# SCH_robot_arm_2022-02-01.net
KiCad netlist of a schematic drawn in EasyEDA
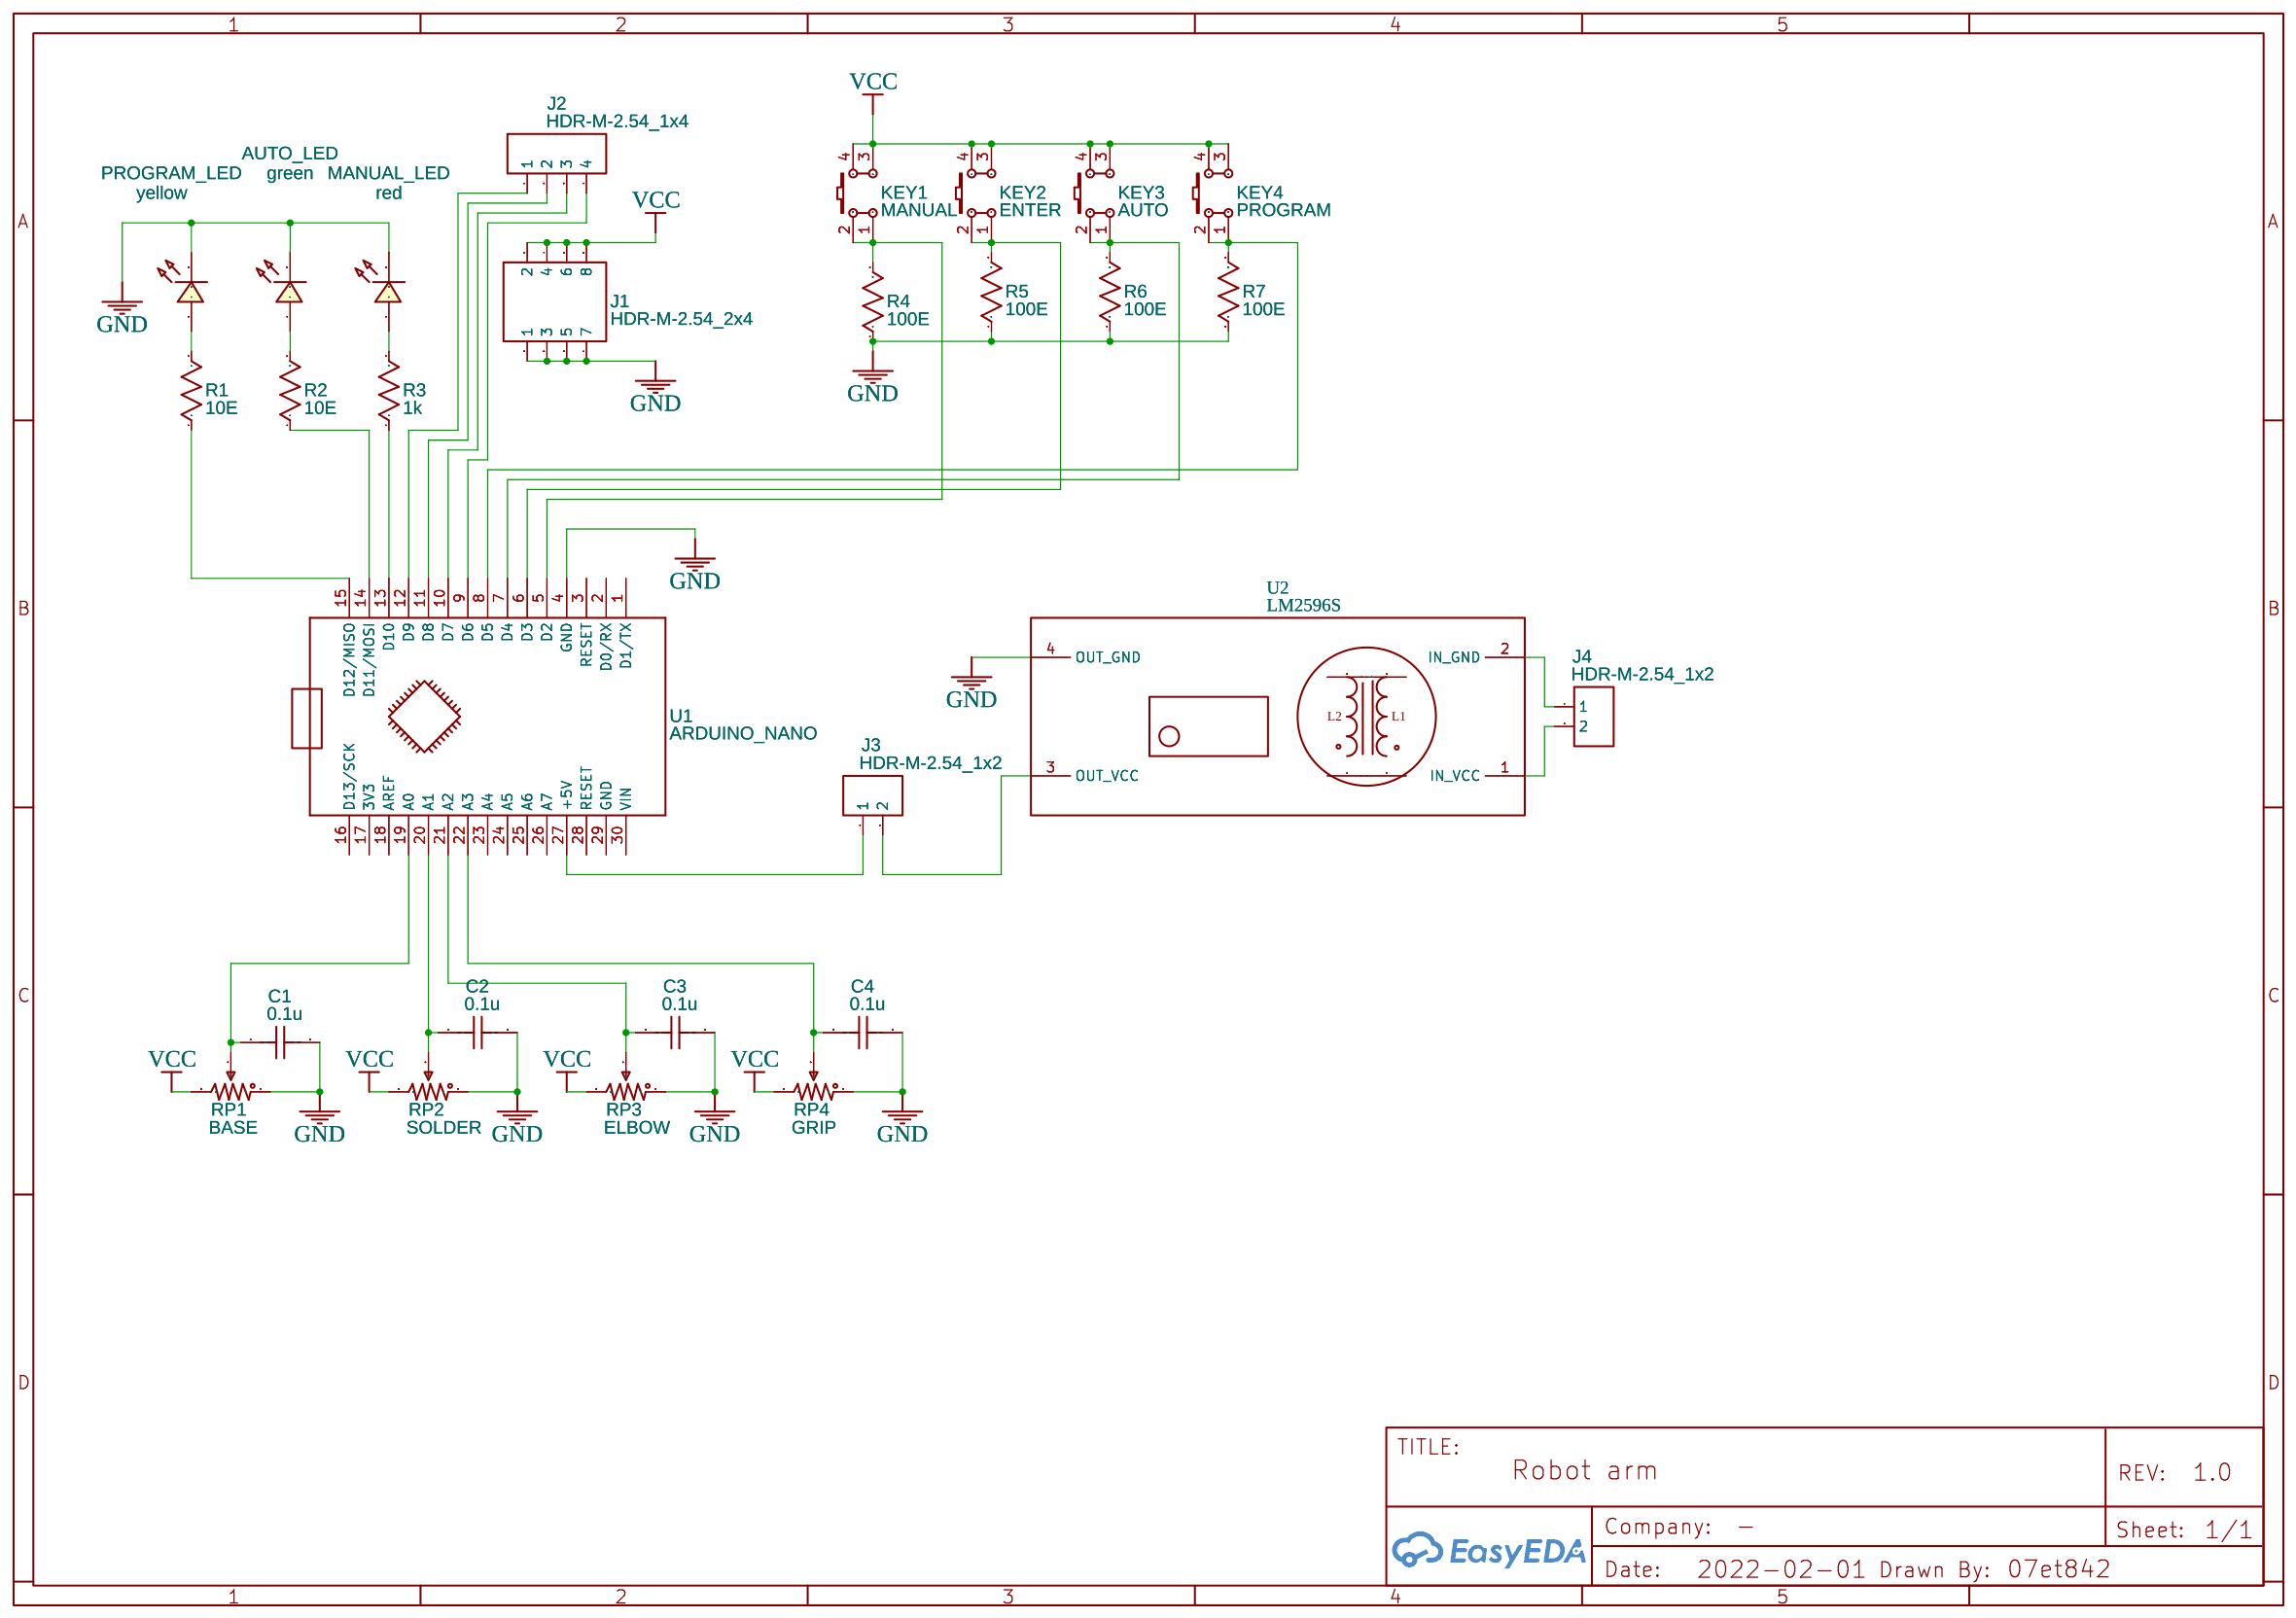
[diagram p0: schematic sheet]

(export (version "E")
  (design (tool "Eeschema 10.0.6"))
  (components
    (comp (ref "AUTO_LED")
      (value "green")
      (fields
        (field (name "BOM_Manufacturer Part") "19-217/R6C-AL1M2VY/3T")
        (field (name "BOM_Supplier Part") "C72044")
      )
      (libsource (lib "") (part "LED-0603_R_1"))
    )
    (comp (ref "C1") (value "0.1u") (libsource (lib "") (part "C_0603_US")))
    (comp (ref "C2") (value "0.1u") (libsource (lib "") (part "C_0603_US")))
    (comp (ref "C3") (value "0.1u") (libsource (lib "") (part "C_0603_US")))
    (comp (ref "C4") (value "0.1u") (libsource (lib "") (part "C_0603_US")))
    (comp (ref "J1")
      (value "HDR-M-2.54_2x4")
      (fields (field (name "BOM_Supplier Part") "C58363"))
      (libsource (lib "") (part "HDR-M-2.54_2x4"))
    )
    (comp (ref "J2")
      (value "HDR-M-2.54_1x4")
      (fields (field (name "BOM_Supplier Part") "C124378"))
      (libsource (lib "") (part "HDR-M-2.54_1x4"))
    )
    (comp (ref "J3")
      (value "HDR-M-2.54_1x2")
      (fields (field (name "BOM_Supplier Part") "C124375"))
      (libsource (lib "") (part "HDR-M-2.54_1x2"))
    )
    (comp (ref "J4")
      (value "HDR-M-2.54_1x2")
      (fields (field (name "BOM_Supplier Part") "C124375"))
      (libsource (lib "") (part "HDR-M-2.54_1x2_1"))
    )
    (comp (ref "KEY1")
      (value "MANUAL")
      (fields
        (field (name "BOM_Manufacturer Part") "K2-1102DP-E4SW-04")
        (field (name "BOM_Supplier Part") "C136684")
      )
      (libsource (lib "") (part "K4-6×6_TH"))
    )
    (comp (ref "KEY2")
      (value "ENTER")
      (fields
        (field (name "BOM_Manufacturer Part") "K2-1102DP-E4SW-04")
        (field (name "BOM_Supplier Part") "C136684")
      )
      (libsource (lib "") (part "K4-6×6_TH"))
    )
    (comp (ref "KEY3")
      (value "AUTO")
      (fields
        (field (name "BOM_Manufacturer Part") "K2-1102DP-E4SW-04")
        (field (name "BOM_Supplier Part") "C136684")
      )
      (libsource (lib "") (part "K4-6×6_TH"))
    )
    (comp (ref "KEY4")
      (value "PROGRAM")
      (fields
        (field (name "BOM_Manufacturer Part") "K2-1102DP-E4SW-04")
        (field (name "BOM_Supplier Part") "C136684")
      )
      (libsource (lib "") (part "K4-6×6_TH"))
    )
    (comp (ref "MANUAL_LED")
      (value "red")
      (fields
        (field (name "BOM_Manufacturer Part") "19-217/R6C-AL1M2VY/3T")
        (field (name "BOM_Supplier Part") "C72044")
      )
      (libsource (lib "") (part "LED-0603_R_2"))
    )
    (comp (ref "PROGRAM_LED")
      (value "yellow")
      (fields
        (field (name "BOM_Manufacturer Part") "19-217/R6C-AL1M2VY/3T")
        (field (name "BOM_Supplier Part") "C72044")
      )
      (libsource (lib "") (part "LED-0603_R"))
    )
    (comp (ref "R1") (value "10E") (libsource (lib "") (part "R_0603_US")))
    (comp (ref "R2") (value "10E") (libsource (lib "") (part "R_0603_US")))
    (comp (ref "R3") (value "1k") (libsource (lib "") (part "R_0603_US")))
    (comp (ref "R4") (value "100E") (libsource (lib "") (part "R_0603_US")))
    (comp (ref "R5") (value "100E") (libsource (lib "") (part "R_0603_US")))
    (comp (ref "R6") (value "100E") (libsource (lib "") (part "R_0603_US")))
    (comp (ref "R7") (value "100E") (libsource (lib "") (part "R_0603_US")))
    (comp (ref "RP1") (value "BASE") (libsource (lib "") (part "R_3386P_US")))
    (comp (ref "RP2") (value "SOLDER") (libsource (lib "") (part "R_3386P_US")))
    (comp (ref "RP3") (value "ELBOW") (libsource (lib "") (part "R_3386P_US")))
    (comp (ref "RP4") (value "GRIP") (libsource (lib "") (part "R_3386P_US")))
    (comp (ref "U1")
      (value "ARDUINO_NANO")
      (fields (field (name "BOM_Manufacturer Part") "?"))
      (libsource (lib "") (part "Unknown_240_-450"))
    )
    (comp (ref "U2") (value "LM2596S") (libsource (lib "") (part "Unknown_645_-450")))
  )
  (nets
    (net (code "1") (name "GND") (class "Default")
      (node (ref "AUTO_LED") (pin "2") (pinfunction "2_2") (pintype "unspecified"))
      (node (ref "C1") (pin "2") (pinfunction "2_2") (pintype "unspecified"))
      (node (ref "C2") (pin "2") (pinfunction "2_2") (pintype "unspecified"))
      (node (ref "C3") (pin "2") (pinfunction "2_2") (pintype "unspecified"))
      (node (ref "C4") (pin "2") (pinfunction "2_2") (pintype "unspecified"))
      (node (ref "J1") (pin "1") (pinfunction "1_1") (pintype "unspecified"))
      (node (ref "J1") (pin "3") (pinfunction "3_3") (pintype "unspecified"))
      (node (ref "J1") (pin "5") (pinfunction "5_5") (pintype "unspecified"))
      (node (ref "J1") (pin "7") (pinfunction "7_7") (pintype "unspecified"))
      (node (ref "MANUAL_LED") (pin "2") (pinfunction "2_2") (pintype "unspecified"))
      (node (ref "PROGRAM_LED") (pin "2") (pinfunction "2_2") (pintype "unspecified"))
      (node (ref "R4") (pin "1") (pinfunction "1_1") (pintype "unspecified"))
      (node (ref "R5") (pin "1") (pinfunction "1_1") (pintype "unspecified"))
      (node (ref "R6") (pin "1") (pinfunction "1_1") (pintype "unspecified"))
      (node (ref "R7") (pin "1") (pinfunction "1_1") (pintype "unspecified"))
      (node (ref "RP1") (pin "1") (pinfunction "1_1") (pintype "unspecified"))
      (node (ref "RP2") (pin "1") (pinfunction "1_1") (pintype "unspecified"))
      (node (ref "RP3") (pin "1") (pinfunction "1_1") (pintype "unspecified"))
      (node (ref "RP4") (pin "1") (pinfunction "1_1") (pintype "unspecified"))
      (node (ref "U1") (pin "4") (pinfunction "GND_4") (pintype "unspecified"))
      (node (ref "U2") (pin "4") (pinfunction "OUT_GND_4") (pintype "unspecified"))
    )
    (net (code "2") (name "Net-(AUTO_LED-Pad1)") (class "Default")
      (node (ref "AUTO_LED") (pin "1") (pinfunction "1_1") (pintype "unspecified"))
      (node (ref "R2") (pin "2") (pinfunction "2_2") (pintype "unspecified"))
    )
    (net (code "3") (name "Net-(MANUAL_LED-Pad1)") (class "Default")
      (node (ref "MANUAL_LED") (pin "1") (pinfunction "1_1") (pintype "unspecified"))
      (node (ref "R3") (pin "2") (pinfunction "2_2") (pintype "unspecified"))
    )
    (net (code "4") (name "Net-(PROGRAM_LED-Pad1)") (class "Default")
      (node (ref "PROGRAM_LED") (pin "1") (pinfunction "1_1") (pintype "unspecified"))
      (node (ref "R1") (pin "2") (pinfunction "2_2") (pintype "unspecified"))
    )
    (net (code "5") (name "Net-(U1-+5V)") (class "Default")
      (node (ref "J3") (pin "1") (pinfunction "1_1") (pintype "unspecified"))
      (node (ref "U1") (pin "27") (pinfunction "+5V_27") (pintype "unspecified"))
    )
    (net (code "6") (name "Net-(U1-A0)") (class "Default")
      (node (ref "C1") (pin "1") (pinfunction "1_1") (pintype "unspecified"))
      (node (ref "RP1") (pin "2") (pinfunction "2_2") (pintype "unspecified"))
      (node (ref "U1") (pin "19") (pinfunction "A0_19") (pintype "unspecified"))
    )
    (net (code "7") (name "Net-(U1-A1)") (class "Default")
      (node (ref "C2") (pin "1") (pinfunction "1_1") (pintype "unspecified"))
      (node (ref "RP2") (pin "2") (pinfunction "2_2") (pintype "unspecified"))
      (node (ref "U1") (pin "20") (pinfunction "A1_20") (pintype "unspecified"))
    )
    (net (code "8") (name "Net-(U1-A2)") (class "Default")
      (node (ref "C3") (pin "1") (pinfunction "1_1") (pintype "unspecified"))
      (node (ref "RP3") (pin "2") (pinfunction "2_2") (pintype "unspecified"))
      (node (ref "U1") (pin "21") (pinfunction "A2_21") (pintype "unspecified"))
    )
    (net (code "9") (name "Net-(U1-A3)") (class "Default")
      (node (ref "C4") (pin "1") (pinfunction "1_1") (pintype "unspecified"))
      (node (ref "RP4") (pin "2") (pinfunction "2_2") (pintype "unspecified"))
      (node (ref "U1") (pin "22") (pinfunction "A3_22") (pintype "unspecified"))
    )
    (net (code "10") (name "Net-(U1-D2)") (class "Default")
      (node (ref "KEY1") (pin "1") (pinfunction "1_1") (pintype "unspecified"))
      (node (ref "KEY1") (pin "2") (pinfunction "2_2") (pintype "unspecified"))
      (node (ref "R4") (pin "2") (pinfunction "2_2") (pintype "unspecified"))
      (node (ref "U1") (pin "5") (pinfunction "D2_5") (pintype "unspecified"))
    )
    (net (code "11") (name "Net-(U1-D3)") (class "Default")
      (node (ref "KEY2") (pin "1") (pinfunction "1_1") (pintype "unspecified"))
      (node (ref "KEY2") (pin "2") (pinfunction "2_2") (pintype "unspecified"))
      (node (ref "R5") (pin "2") (pinfunction "2_2") (pintype "unspecified"))
      (node (ref "U1") (pin "6") (pinfunction "D3_6") (pintype "unspecified"))
    )
    (net (code "12") (name "Net-(U1-D4)") (class "Default")
      (node (ref "KEY3") (pin "1") (pinfunction "1_1") (pintype "unspecified"))
      (node (ref "KEY3") (pin "2") (pinfunction "2_2") (pintype "unspecified"))
      (node (ref "R6") (pin "2") (pinfunction "2_2") (pintype "unspecified"))
      (node (ref "U1") (pin "7") (pinfunction "D4_7") (pintype "unspecified"))
    )
    (net (code "13") (name "Net-(U1-D5)") (class "Default")
      (node (ref "KEY4") (pin "1") (pinfunction "1_1") (pintype "unspecified"))
      (node (ref "KEY4") (pin "2") (pinfunction "2_2") (pintype "unspecified"))
      (node (ref "R7") (pin "2") (pinfunction "2_2") (pintype "unspecified"))
      (node (ref "U1") (pin "8") (pinfunction "D5_8") (pintype "unspecified"))
    )
    (net (code "14") (name "Net-(U1-D6)") (class "Default")
      (node (ref "J2") (pin "4") (pinfunction "4_4") (pintype "unspecified"))
      (node (ref "U1") (pin "9") (pinfunction "D6_9") (pintype "unspecified"))
    )
    (net (code "15") (name "Net-(U1-D7)") (class "Default")
      (node (ref "J2") (pin "3") (pinfunction "3_3") (pintype "unspecified"))
      (node (ref "U1") (pin "10") (pinfunction "D7_10") (pintype "unspecified"))
    )
    (net (code "16") (name "Net-(U1-D8)") (class "Default")
      (node (ref "J2") (pin "2") (pinfunction "2_2") (pintype "unspecified"))
      (node (ref "U1") (pin "11") (pinfunction "D8_11") (pintype "unspecified"))
    )
    (net (code "17") (name "Net-(U1-D9)") (class "Default")
      (node (ref "J2") (pin "1") (pinfunction "1_1") (pintype "unspecified"))
      (node (ref "U1") (pin "12") (pinfunction "D9_12") (pintype "unspecified"))
    )
    (net (code "18") (name "Net-(U1-D10)") (class "Default")
      (node (ref "R3") (pin "1") (pinfunction "1_1") (pintype "unspecified"))
      (node (ref "U1") (pin "13") (pinfunction "D10_13") (pintype "unspecified"))
    )
    (net (code "19") (name "Net-(U1-D11{slash}MOSI)") (class "Default")
      (node (ref "R2") (pin "1") (pinfunction "1_1") (pintype "unspecified"))
      (node (ref "U1") (pin "14") (pinfunction "D11/MOSI_14") (pintype "unspecified"))
    )
    (net (code "20") (name "Net-(U1-D12{slash}MISO)") (class "Default")
      (node (ref "R1") (pin "1") (pinfunction "1_1") (pintype "unspecified"))
      (node (ref "U1") (pin "15") (pinfunction "D12/MISO_15") (pintype "unspecified"))
    )
    (net (code "21") (name "Net-(U2-IN_GND)") (class "Default")
      (node (ref "J4") (pin "1") (pinfunction "1_1") (pintype "unspecified"))
      (node (ref "U2") (pin "2") (pinfunction "IN_GND_2") (pintype "unspecified"))
    )
    (net (code "22") (name "Net-(U2-IN_VCC)") (class "Default")
      (node (ref "J4") (pin "2") (pinfunction "2_2") (pintype "unspecified"))
      (node (ref "U2") (pin "1") (pinfunction "IN_VCC_1") (pintype "unspecified"))
    )
    (net (code "23") (name "Net-(U2-OUT_VCC)") (class "Default")
      (node (ref "J3") (pin "2") (pinfunction "2_2") (pintype "unspecified"))
      (node (ref "U2") (pin "3") (pinfunction "OUT_VCC_3") (pintype "unspecified"))
    )
    (net (code "24") (name "VCC") (class "Default")
      (node (ref "J1") (pin "2") (pinfunction "2_2") (pintype "unspecified"))
      (node (ref "J1") (pin "4") (pinfunction "4_4") (pintype "unspecified"))
      (node (ref "J1") (pin "6") (pinfunction "6_6") (pintype "unspecified"))
      (node (ref "J1") (pin "8") (pinfunction "8_8") (pintype "unspecified"))
      (node (ref "KEY1") (pin "3") (pinfunction "3_3") (pintype "unspecified"))
      (node (ref "KEY1") (pin "4") (pinfunction "4_4") (pintype "unspecified"))
      (node (ref "KEY2") (pin "3") (pinfunction "3_3") (pintype "unspecified"))
      (node (ref "KEY2") (pin "4") (pinfunction "4_4") (pintype "unspecified"))
      (node (ref "KEY3") (pin "3") (pinfunction "3_3") (pintype "unspecified"))
      (node (ref "KEY3") (pin "4") (pinfunction "4_4") (pintype "unspecified"))
      (node (ref "KEY4") (pin "3") (pinfunction "3_3") (pintype "unspecified"))
      (node (ref "KEY4") (pin "4") (pinfunction "4_4") (pintype "unspecified"))
      (node (ref "RP1") (pin "3") (pinfunction "3_3") (pintype "unspecified"))
      (node (ref "RP2") (pin "3") (pinfunction "3_3") (pintype "unspecified"))
      (node (ref "RP3") (pin "3") (pinfunction "3_3") (pintype "unspecified"))
      (node (ref "RP4") (pin "3") (pinfunction "3_3") (pintype "unspecified"))
    )
    (net (code "25") (name "unconnected-(U1-3V3-Pad17)") (class "Default")
      (node (ref "U1") (pin "17") (pinfunction "3V3_17") (pintype "unspecified"))
    )
    (net (code "26") (name "unconnected-(U1-A4-Pad23)") (class "Default")
      (node (ref "U1") (pin "23") (pinfunction "A4_23") (pintype "unspecified"))
    )
    (net (code "27") (name "unconnected-(U1-A5-Pad24)") (class "Default")
      (node (ref "U1") (pin "24") (pinfunction "A5_24") (pintype "unspecified"))
    )
    (net (code "28") (name "unconnected-(U1-A6-Pad25)") (class "Default")
      (node (ref "U1") (pin "25") (pinfunction "A6_25") (pintype "unspecified"))
    )
    (net (code "29") (name "unconnected-(U1-A7-Pad26)") (class "Default")
      (node (ref "U1") (pin "26") (pinfunction "A7_26") (pintype "unspecified"))
    )
    (net (code "30") (name "unconnected-(U1-AREF-Pad18)") (class "Default")
      (node (ref "U1") (pin "18") (pinfunction "AREF_18") (pintype "unspecified"))
    )
    (net (code "31") (name "unconnected-(U1-D0{slash}RX-Pad2)") (class "Default")
      (node (ref "U1") (pin "2") (pinfunction "D0/RX_2") (pintype "unspecified"))
    )
    (net (code "32") (name "unconnected-(U1-D1{slash}TX-Pad1)") (class "Default")
      (node (ref "U1") (pin "1") (pinfunction "D1/TX_1") (pintype "unspecified"))
    )
    (net (code "33") (name "unconnected-(U1-D13{slash}SCK-Pad16)") (class "Default")
      (node (ref "U1") (pin "16") (pinfunction "D13/SCK_16") (pintype "unspecified"))
    )
    (net (code "34") (name "unconnected-(U1-GND-Pad29)") (class "Default")
      (node (ref "U1") (pin "29") (pinfunction "GND_29") (pintype "unspecified"))
    )
    (net (code "35") (name "unconnected-(U1-RESET-Pad3)") (class "Default")
      (node (ref "U1") (pin "3") (pinfunction "RESET_3") (pintype "unspecified"))
    )
    (net (code "36") (name "unconnected-(U1-RESET-Pad28)") (class "Default")
      (node (ref "U1") (pin "28") (pinfunction "RESET_28") (pintype "unspecified"))
    )
    (net (code "37") (name "unconnected-(U1-VIN-Pad30)") (class "Default")
      (node (ref "U1") (pin "30") (pinfunction "VIN_30") (pintype "unspecified"))
    )
    (net (code "38") (name "unconnected-(U2-1_-Pad1)") (class "Default")
      (node (ref "U2") (pin "1") (pinfunction "1__1") (pintype "unspecified"))
    )
    (net (code "39") (name "unconnected-(U2-2_-Pad2)") (class "Default")
      (node (ref "U2") (pin "2") (pinfunction "2__2") (pintype "unspecified"))
    )
    (net (code "40") (name "unconnected-(U2-3_-Pad3)") (class "Default")
      (node (ref "U2") (pin "3") (pinfunction "3__3") (pintype "unspecified"))
    )
    (net (code "41") (name "unconnected-(U2-4_-Pad4)") (class "Default")
      (node (ref "U2") (pin "4") (pinfunction "4__4") (pintype "unspecified"))
    )
  )
)
